# 2015_FDP_PROPULSION.net
KiCad netlist of a schematic drawn in Altium Designer
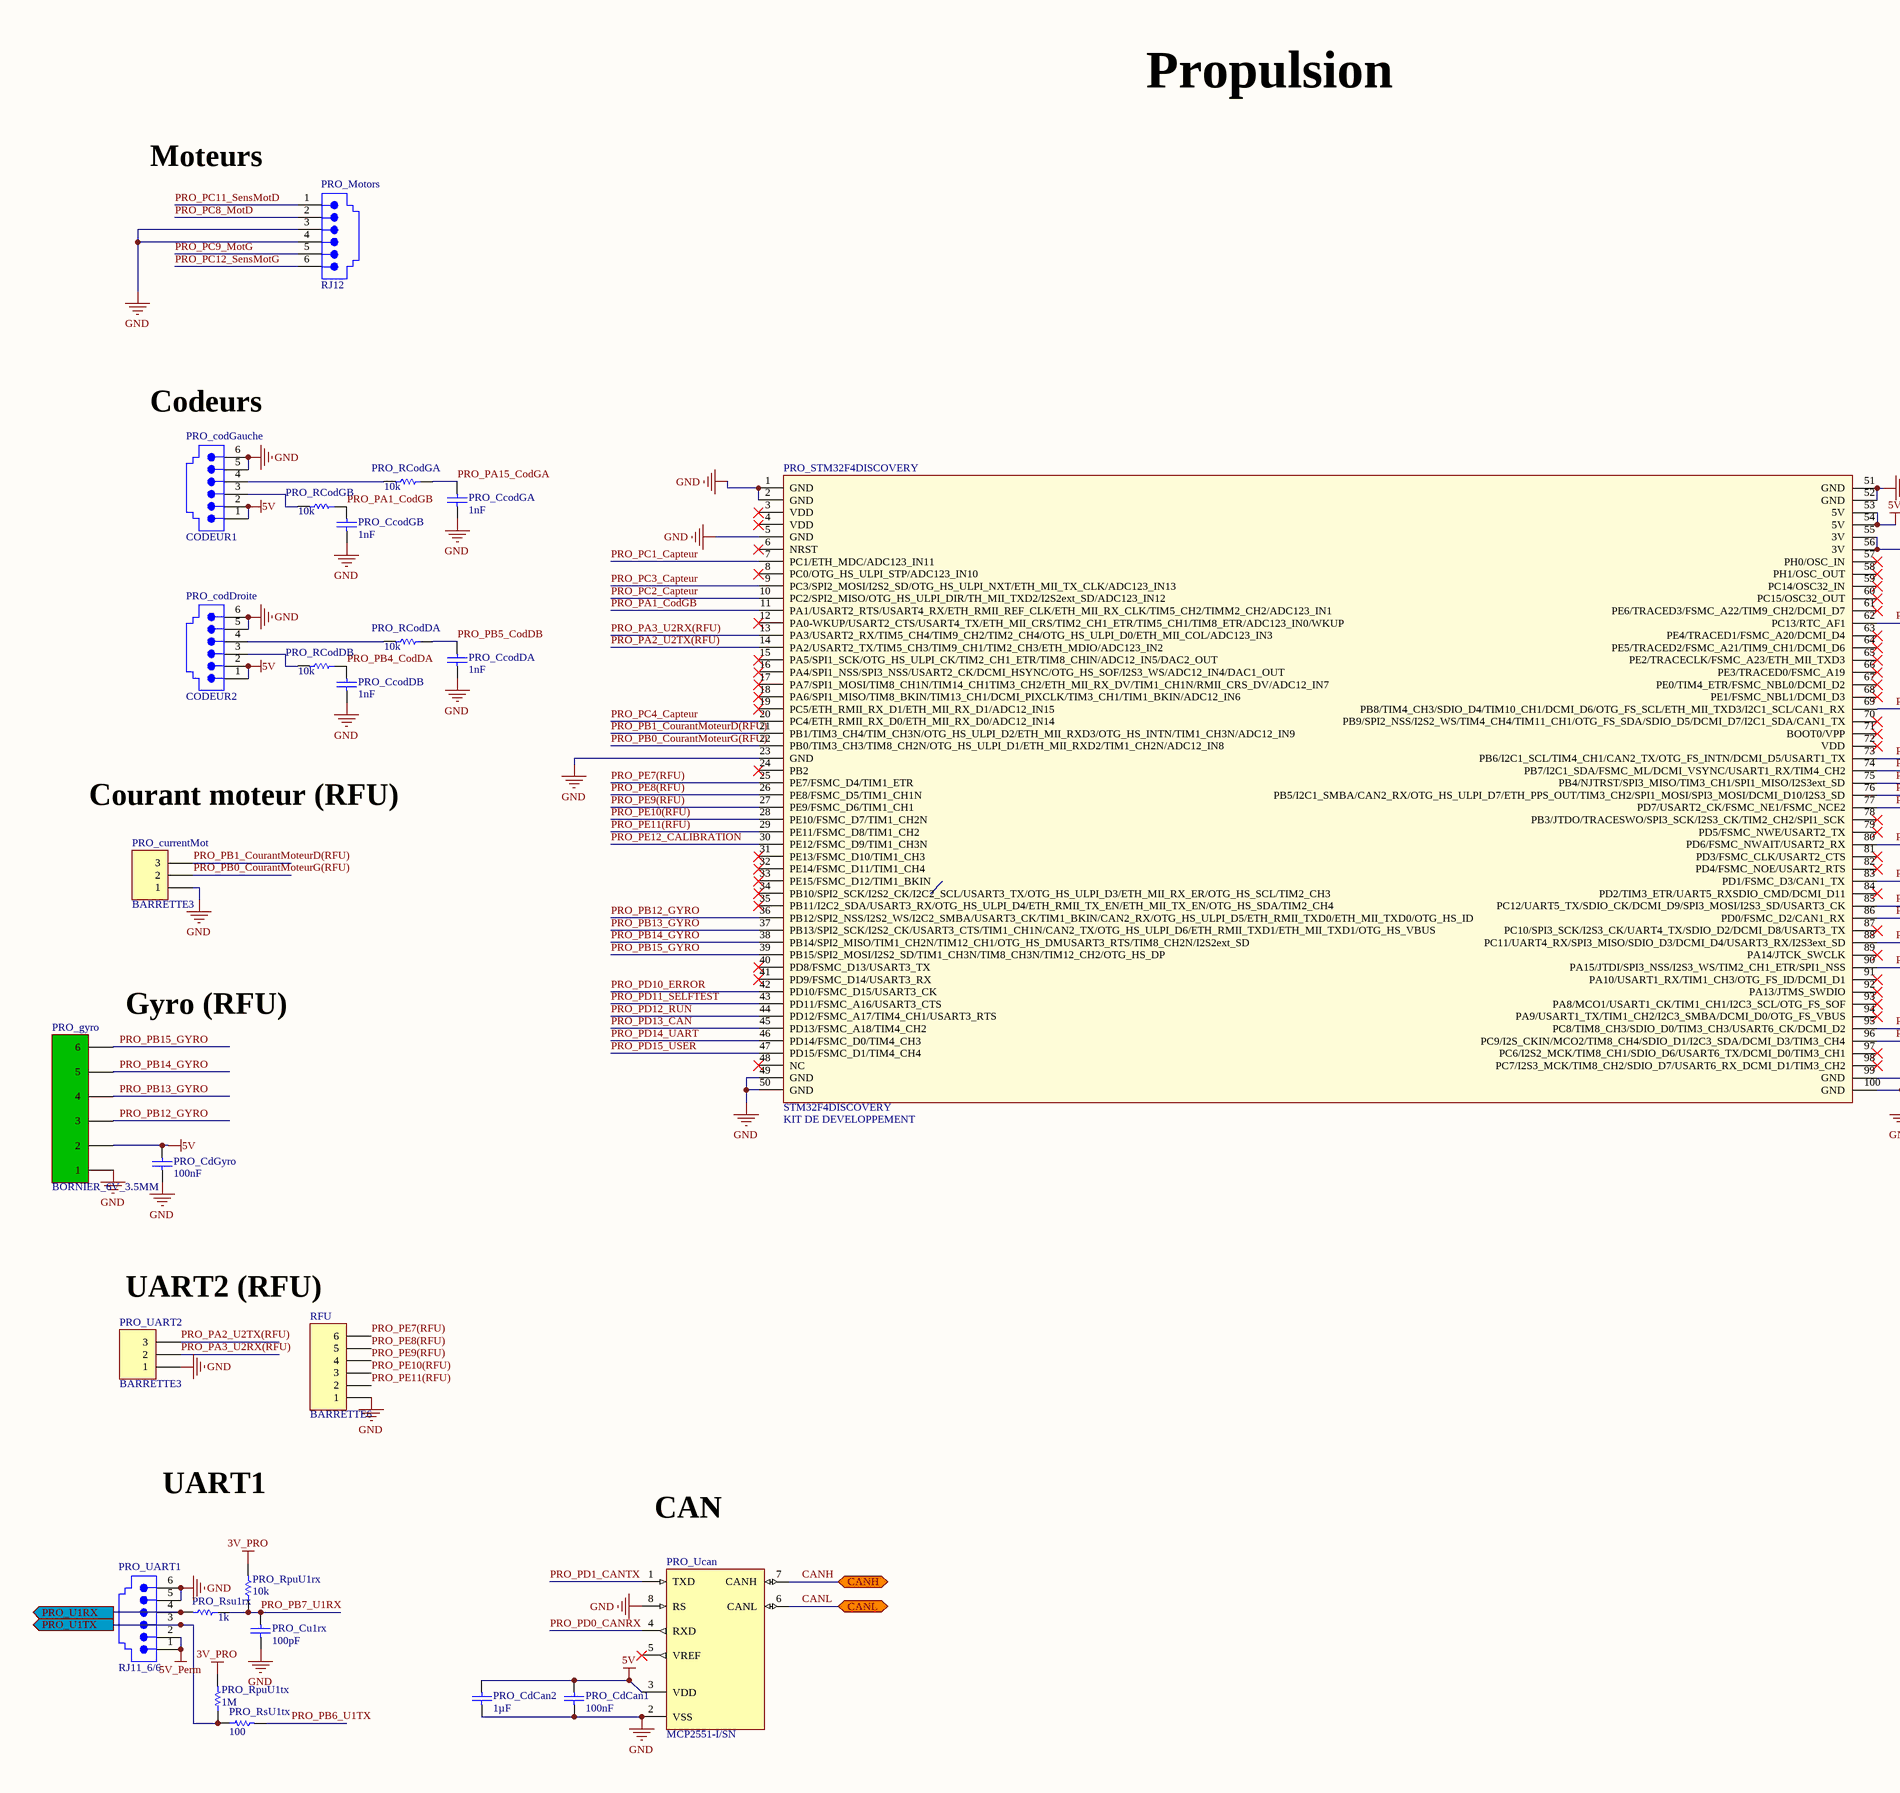
[diagram p0: 2015_FDP_PROPULSION.SchDoc, left]
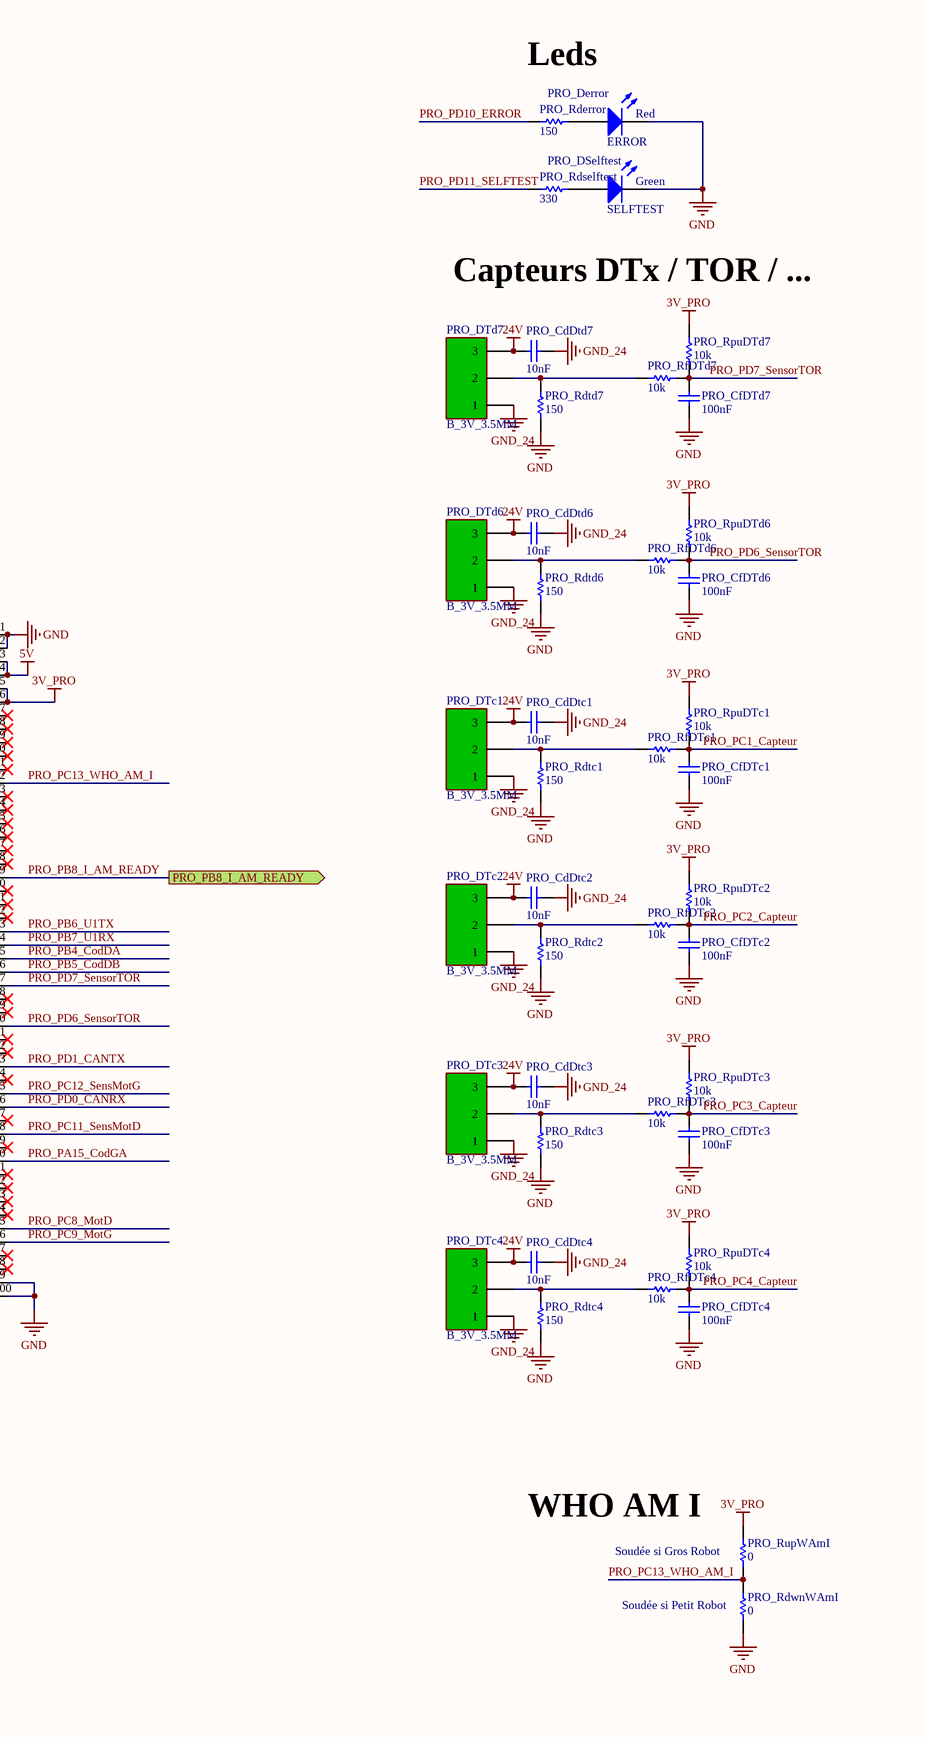
[diagram p1: 2015_FDP_PROPULSION.SchDoc, right]

(export (version "E")
  (design (tool "Eeschema 10.0.6"))
  (components
    (comp (ref "PRO_CcodDA")
      (value "1nF")
      (footprint "C0805_N")
      (description "Capacitor")
      (fields (field (name "PUBLISHER") "Altium Limited"))
      (libsource (lib "_ROBOT") (part "Condensateur"))
    )
    (comp (ref "PRO_CcodDB")
      (value "1nF")
      (footprint "C0805_N")
      (description "Capacitor")
      (fields (field (name "PUBLISHER") "Altium Limited"))
      (libsource (lib "_ROBOT") (part "Condensateur"))
    )
    (comp (ref "PRO_CcodGA")
      (value "1nF")
      (footprint "C0805_N")
      (description "Capacitor")
      (fields (field (name "PUBLISHER") "Altium Limited"))
      (libsource (lib "_ROBOT") (part "Condensateur"))
    )
    (comp (ref "PRO_CcodGB")
      (value "1nF")
      (footprint "C0805_N")
      (description "Capacitor")
      (fields (field (name "PUBLISHER") "Altium Limited"))
      (libsource (lib "_ROBOT") (part "Condensateur"))
    )
    (comp (ref "PRO_CdCan1")
      (value "100nF")
      (footprint "C0805_N")
      (description "Capacitor")
      (fields (field (name "PUBLISHER") "Altium Limited"))
      (libsource (lib "_ROBOT") (part "Condensateur"))
    )
    (comp (ref "PRO_CdCan2")
      (value "1µF")
      (footprint "C0805_N")
      (description "Capacitor")
      (fields (field (name "PUBLISHER") "Altium Limited"))
      (libsource (lib "_ROBOT") (part "Condensateur"))
    )
    (comp (ref "PRO_CdDtc1")
      (value "10nF")
      (footprint "C0805_N")
      (description "Capacitor")
      (fields (field (name "PUBLISHER") "Altium Limited"))
      (libsource (lib "_ROBOT") (part "Condensateur"))
    )
    (comp (ref "PRO_CdDtc2")
      (value "10nF")
      (footprint "C0805_N")
      (description "Capacitor")
      (fields (field (name "PUBLISHER") "Altium Limited"))
      (libsource (lib "_ROBOT") (part "Condensateur"))
    )
    (comp (ref "PRO_CdDtc3")
      (value "10nF")
      (footprint "C0805_N")
      (description "Capacitor")
      (fields (field (name "PUBLISHER") "Altium Limited"))
      (libsource (lib "_ROBOT") (part "Condensateur"))
    )
    (comp (ref "PRO_CdDtc4")
      (value "10nF")
      (footprint "C0805_N")
      (description "Capacitor")
      (fields (field (name "PUBLISHER") "Altium Limited"))
      (libsource (lib "_ROBOT") (part "Condensateur"))
    )
    (comp (ref "PRO_CdDtd6")
      (value "10nF")
      (footprint "C0805_N")
      (description "Capacitor")
      (fields (field (name "PUBLISHER") "Altium Limited"))
      (libsource (lib "_ROBOT") (part "Condensateur"))
    )
    (comp (ref "PRO_CdDtd7")
      (value "10nF")
      (footprint "C0805_N")
      (description "Capacitor")
      (fields (field (name "PUBLISHER") "Altium Limited"))
      (libsource (lib "_ROBOT") (part "Condensateur"))
    )
    (comp (ref "PRO_CdGyro")
      (value "100nF")
      (footprint "C0805_N")
      (description "Capacitor")
      (fields (field (name "PUBLISHER") "Altium Limited"))
      (libsource (lib "_ROBOT") (part "Condensateur"))
    )
    (comp (ref "PRO_CfDTc1")
      (value "100nF")
      (footprint "C0805_N")
      (description "Capacitor")
      (fields (field (name "PUBLISHER") "Altium Limited"))
      (libsource (lib "_ROBOT") (part "Condensateur"))
    )
    (comp (ref "PRO_CfDTc2")
      (value "100nF")
      (footprint "C0805_N")
      (description "Capacitor")
      (fields (field (name "PUBLISHER") "Altium Limited"))
      (libsource (lib "_ROBOT") (part "Condensateur"))
    )
    (comp (ref "PRO_CfDTc3")
      (value "100nF")
      (footprint "C0805_N")
      (description "Capacitor")
      (fields (field (name "PUBLISHER") "Altium Limited"))
      (libsource (lib "_ROBOT") (part "Condensateur"))
    )
    (comp (ref "PRO_CfDTc4")
      (value "100nF")
      (footprint "C0805_N")
      (description "Capacitor")
      (fields (field (name "PUBLISHER") "Altium Limited"))
      (libsource (lib "_ROBOT") (part "Condensateur"))
    )
    (comp (ref "PRO_CfDTd6")
      (value "100nF")
      (footprint "C0805_N")
      (description "Capacitor")
      (fields (field (name "PUBLISHER") "Altium Limited"))
      (libsource (lib "_ROBOT") (part "Condensateur"))
    )
    (comp (ref "PRO_CfDTd7")
      (value "100nF")
      (footprint "C0805_N")
      (description "Capacitor")
      (fields (field (name "PUBLISHER") "Altium Limited"))
      (libsource (lib "_ROBOT") (part "Condensateur"))
    )
    (comp (ref "PRO_codDroite")
      (value "CODEUR2")
      (footprint "RJ11_6/6 - droit")
      (description "Right Angle, Standard Profile, Offset Latch DECconnect, Flangeless PCB Jack")
      (fields (field (name "PUBLISHER") "Altium Limited"))
      (libsource (lib "miniprojet") (part "RJ11_6/6"))
    )
    (comp (ref "PRO_codGauche")
      (value "CODEUR1")
      (footprint "RJ11_6/6 - droit")
      (description "Right Angle, Standard Profile, Offset Latch DECconnect, Flangeless PCB Jack")
      (fields (field (name "PUBLISHER") "Altium Limited"))
      (libsource (lib "miniprojet") (part "RJ11_6/6"))
    )
    (comp (ref "PRO_Cu1rx")
      (value "100pF")
      (footprint "C0805_N")
      (description "Capacitor")
      (fields (field (name "PUBLISHER") "Altium Limited"))
      (libsource (lib "_ROBOT") (part "Condensateur"))
    )
    (comp (ref "PRO_currentMot")
      (value "BARRETTE3")
      (footprint "HE14_3")
      (description "Header, 3-Pin")
      (fields (field (name "PUBLISHER") "Altium Limited"))
      (libsource (lib "Connecteur") (part "BARRETTE3"))
    )
    (comp (ref "PRO_Derror")
      (value "ERROR")
      (footprint "LED_0805")
      (description "Typical LED")
      (fields (field (name "PUBLISHER") "Altium Limited"))
      (libsource (lib "_ROBOT") (part "LED"))
    )
    (comp (ref "PRO_DSelftest")
      (value "SELFTEST")
      (footprint "LED_0805")
      (description "Typical LED")
      (fields (field (name "PUBLISHER") "Altium Limited"))
      (libsource (lib "_ROBOT") (part "LED"))
    )
    (comp (ref "PRO_DTc1")
      (value "B_3V_3.5MM")
      (footprint "BORNIER_3V_3.5MM")
      (libsource (lib "Connecteur") (part "BORNIER_3V_3.5MM"))
    )
    (comp (ref "PRO_DTc2")
      (value "B_3V_3.5MM")
      (footprint "BORNIER_3V_3.5MM")
      (libsource (lib "Connecteur") (part "BORNIER_3V_3.5MM"))
    )
    (comp (ref "PRO_DTc3")
      (value "B_3V_3.5MM")
      (footprint "BORNIER_3V_3.5MM")
      (libsource (lib "Connecteur") (part "BORNIER_3V_3.5MM"))
    )
    (comp (ref "PRO_DTc4")
      (value "B_3V_3.5MM")
      (footprint "BORNIER_3V_3.5MM")
      (libsource (lib "Connecteur") (part "BORNIER_3V_3.5MM"))
    )
    (comp (ref "PRO_DTd6")
      (value "B_3V_3.5MM")
      (footprint "BORNIER_3V_3.5MM")
      (libsource (lib "Connecteur") (part "BORNIER_3V_3.5MM"))
    )
    (comp (ref "PRO_DTd7")
      (value "B_3V_3.5MM")
      (footprint "BORNIER_3V_3.5MM")
      (libsource (lib "Connecteur") (part "BORNIER_3V_3.5MM"))
    )
    (comp (ref "PRO_gyro")
      (value "BORNIER_6V_3.5MM")
      (footprint "BORNIER_6V_3.5MM")
      (libsource (lib "Connecteur") (part "BORNIER_6V_3.5MM"))
    )
    (comp (ref "PRO_Motors")
      (value "RJ12")
      (footprint "RJ11_6/6 - droit")
      (description "Right Angle, Standard Profile, Offset Latch DECconnect, Flangeless PCB Jack")
      (fields (field (name "PUBLISHER") "Altium Limited"))
      (libsource (lib "Connecteur") (part "RJ11_6/6"))
    )
    (comp (ref "PRO_RCodDA")
      (value "10k")
      (footprint "R1206_N")
      (description "Resistor")
      (fields (field (name "PUBLISHER") "Altium Limited"))
      (libsource (lib "_ROBOT") (part "Resistor"))
    )
    (comp (ref "PRO_RCodDB")
      (value "10k")
      (footprint "R1206_N")
      (description "Resistor")
      (fields (field (name "PUBLISHER") "Altium Limited"))
      (libsource (lib "_ROBOT") (part "Resistor"))
    )
    (comp (ref "PRO_RCodGA")
      (value "10k")
      (footprint "R1206_N")
      (description "Resistor")
      (fields (field (name "PUBLISHER") "Altium Limited"))
      (libsource (lib "_ROBOT") (part "Resistor"))
    )
    (comp (ref "PRO_RCodGB")
      (value "10k")
      (footprint "R1206_N")
      (description "Resistor")
      (fields (field (name "PUBLISHER") "Altium Limited"))
      (libsource (lib "_ROBOT") (part "Resistor"))
    )
    (comp (ref "PRO_Rderror")
      (value "150")
      (footprint "R1206_N")
      (description "Resistor")
      (fields (field (name "PUBLISHER") "Altium Limited"))
      (libsource (lib "_ROBOT") (part "Resistor"))
    )
    (comp (ref "PRO_Rdselftest")
      (value "330")
      (footprint "R1206_N")
      (description "Resistor")
      (fields (field (name "PUBLISHER") "Altium Limited"))
      (libsource (lib "_ROBOT") (part "Resistor"))
    )
    (comp (ref "PRO_Rdtc1")
      (value "150")
      (footprint "R1206_N")
      (description "Resistor")
      (fields (field (name "PUBLISHER") "Altium Limited"))
      (libsource (lib "_ROBOT") (part "Resistor"))
    )
    (comp (ref "PRO_Rdtc2")
      (value "150")
      (footprint "R1206_N")
      (description "Resistor")
      (fields (field (name "PUBLISHER") "Altium Limited"))
      (libsource (lib "_ROBOT") (part "Resistor"))
    )
    (comp (ref "PRO_Rdtc3")
      (value "150")
      (footprint "R1206_N")
      (description "Resistor")
      (fields (field (name "PUBLISHER") "Altium Limited"))
      (libsource (lib "_ROBOT") (part "Resistor"))
    )
    (comp (ref "PRO_Rdtc4")
      (value "150")
      (footprint "R1206_N")
      (description "Resistor")
      (fields (field (name "PUBLISHER") "Altium Limited"))
      (libsource (lib "_ROBOT") (part "Resistor"))
    )
    (comp (ref "PRO_Rdtd6")
      (value "150")
      (footprint "R1206_N")
      (description "Resistor")
      (fields (field (name "PUBLISHER") "Altium Limited"))
      (libsource (lib "_ROBOT") (part "Resistor"))
    )
    (comp (ref "PRO_Rdtd7")
      (value "150")
      (footprint "R1206_N")
      (description "Resistor")
      (fields (field (name "PUBLISHER") "Altium Limited"))
      (libsource (lib "_ROBOT") (part "Resistor"))
    )
    (comp (ref "PRO_RdwnWAmI")
      (value "0")
      (footprint "R1206_N")
      (description "Resistor")
      (fields (field (name "PUBLISHER") "Altium Limited"))
      (libsource (lib "_ROBOT") (part "Resistor"))
    )
    (comp (ref "PRO_RfDTc1")
      (value "10k")
      (footprint "R1206_N")
      (description "Resistor")
      (fields (field (name "PUBLISHER") "Altium Limited"))
      (libsource (lib "_ROBOT") (part "Resistor"))
    )
    (comp (ref "PRO_RfDTc2")
      (value "10k")
      (footprint "R1206_N")
      (description "Resistor")
      (fields (field (name "PUBLISHER") "Altium Limited"))
      (libsource (lib "_ROBOT") (part "Resistor"))
    )
    (comp (ref "PRO_RfDTc3")
      (value "10k")
      (footprint "R1206_N")
      (description "Resistor")
      (fields (field (name "PUBLISHER") "Altium Limited"))
      (libsource (lib "_ROBOT") (part "Resistor"))
    )
    (comp (ref "PRO_RfDTc4")
      (value "10k")
      (footprint "R1206_N")
      (description "Resistor")
      (fields (field (name "PUBLISHER") "Altium Limited"))
      (libsource (lib "_ROBOT") (part "Resistor"))
    )
    (comp (ref "PRO_RfDTd6")
      (value "10k")
      (footprint "R1206_N")
      (description "Resistor")
      (fields (field (name "PUBLISHER") "Altium Limited"))
      (libsource (lib "_ROBOT") (part "Resistor"))
    )
    (comp (ref "PRO_RfDTd7")
      (value "10k")
      (footprint "R1206_N")
      (description "Resistor")
      (fields (field (name "PUBLISHER") "Altium Limited"))
      (libsource (lib "_ROBOT") (part "Resistor"))
    )
    (comp (ref "PRO_RpuDTc1")
      (value "10k")
      (footprint "R1206_N")
      (description "Resistor")
      (fields (field (name "PUBLISHER") "Altium Limited"))
      (libsource (lib "_ROBOT") (part "Resistor"))
    )
    (comp (ref "PRO_RpuDTc2")
      (value "10k")
      (footprint "R1206_N")
      (description "Resistor")
      (fields (field (name "PUBLISHER") "Altium Limited"))
      (libsource (lib "_ROBOT") (part "Resistor"))
    )
    (comp (ref "PRO_RpuDTc3")
      (value "10k")
      (footprint "R1206_N")
      (description "Resistor")
      (fields (field (name "PUBLISHER") "Altium Limited"))
      (libsource (lib "_ROBOT") (part "Resistor"))
    )
    (comp (ref "PRO_RpuDTc4")
      (value "10k")
      (footprint "R1206_N")
      (description "Resistor")
      (fields (field (name "PUBLISHER") "Altium Limited"))
      (libsource (lib "_ROBOT") (part "Resistor"))
    )
    (comp (ref "PRO_RpuDTd6")
      (value "10k")
      (footprint "R1206_N")
      (description "Resistor")
      (fields (field (name "PUBLISHER") "Altium Limited"))
      (libsource (lib "_ROBOT") (part "Resistor"))
    )
    (comp (ref "PRO_RpuDTd7")
      (value "10k")
      (footprint "R1206_N")
      (description "Resistor")
      (fields (field (name "PUBLISHER") "Altium Limited"))
      (libsource (lib "_ROBOT") (part "Resistor"))
    )
    (comp (ref "PRO_RpuU1rx")
      (value "10k")
      (footprint "R1206_N")
      (description "Resistor")
      (fields (field (name "PUBLISHER") "Altium Limited"))
      (libsource (lib "_ROBOT") (part "Resistor"))
    )
    (comp (ref "PRO_RpuU1tx")
      (value "1M")
      (footprint "R1206_N")
      (description "Resistor")
      (fields (field (name "PUBLISHER") "Altium Limited"))
      (libsource (lib "_ROBOT") (part "Resistor"))
    )
    (comp (ref "PRO_Rsu1rx")
      (value "1k")
      (footprint "R1206_N")
      (description "Resistor")
      (fields (field (name "PUBLISHER") "Altium Limited"))
      (libsource (lib "_ROBOT") (part "Resistor"))
    )
    (comp (ref "PRO_RsU1tx")
      (value "100")
      (footprint "R1206_N")
      (description "Resistor")
      (fields (field (name "PUBLISHER") "Altium Limited"))
      (libsource (lib "_ROBOT") (part "Resistor"))
    )
    (comp (ref "PRO_RupWAmI")
      (value "0")
      (footprint "R1206_N")
      (description "Resistor")
      (fields (field (name "PUBLISHER") "Altium Limited"))
      (libsource (lib "_ROBOT") (part "Resistor"))
    )
    (comp (ref "PRO_STM32F4DISCOVERY")
      (value "STM32F4DISCOVERY")
      (footprint "STM32_F4DISCOVERY")
      (description "KIT DE DEVELOPPEMENT POUR MICROCONTROLEUR STM32F407VGT6")
      (fields (field (name "TYPE") "KIT DE DEVELOPPEMENT"))
      (libsource (lib "circuits integres") (part "STM32F4DISCOVERY"))
    )
    (comp (ref "PRO_UART1")
      (value "RJ11_6/6")
      (footprint "RJ11_6/6 - droit")
      (description "Right Angle, Standard Profile, Offset Latch DECconnect, Flangeless PCB Jack")
      (fields (field (name "PUBLISHER") "Altium Limited"))
      (libsource (lib "Connecteur") (part "RJ11_6/6"))
    )
    (comp (ref "PRO_UART2")
      (value "BARRETTE3")
      (footprint "HE14_3")
      (description "Header, 3-Pin")
      (fields (field (name "PUBLISHER") "Altium Limited"))
      (libsource (lib "Connecteur") (part "BARRETTE3"))
    )
    (comp (ref "PRO_Ucan")
      (value "MCP2551-I/SN")
      (footprint "SO8_N")
      (description "High-Speed CAN Transceiver, 8-Pin SOIC, Industrial Temperature")
      (fields (field (name "PUBLISHER") "Damien Guitton"))
      (libsource (lib "Circuit intégré") (part "MCP2551-I/SN"))
    )
    (comp (ref "RFU")
      (value "BARRETTE6")
      (footprint "HE14_6")
      (description "Header, 6-Pin")
      (fields (field (name "PUBLISHER") "Altium Limited"))
      (libsource (lib "Connecteur") (part "BARRETTE6"))
    )
  )
  (nets
    (net (code "1") (name "/CANH") (class "Default")
      (node (ref "PRO_Ucan") (pin "7") (pinfunction "CANH_7") (pintype "bidirectional"))
    )
    (net (code "2") (name "/CANL") (class "Default")
      (node (ref "PRO_Ucan") (pin "6") (pinfunction "CANL_6") (pintype "bidirectional"))
    )
    (net (code "3") (name "/PRO_PA1_CodGB") (class "Default")
      (node (ref "PRO_CcodGB") (pin "2") (pinfunction "2_2") (pintype "passive"))
      (node (ref "PRO_RCodGB") (pin "1") (pinfunction "1_1") (pintype "passive"))
      (node (ref "PRO_STM32F4DISCOVERY") (pin "11") (pinfunction "PA1/USART2_RTS/USART4_RX/ETH_RMII_REF_CLK/ETH_MII_RX_CLK/TIM5_CH2/TIMM2_CH2/ADC123_IN1_11") (pintype "passive"))
    )
    (net (code "4") (name "/PRO_PA2_U2TX(RFU)") (class "Default")
      (node (ref "PRO_STM32F4DISCOVERY") (pin "14") (pinfunction "PA2/USART2_TX/TIM5_CH3/TIM9_CH1/TIM2_CH3/ETH_MDIO/ADC123_IN2_14") (pintype "passive"))
      (node (ref "PRO_UART2") (pin "3") (pinfunction "3_3") (pintype "passive"))
    )
    (net (code "5") (name "/PRO_PA3_U2RX(RFU)") (class "Default")
      (node (ref "PRO_STM32F4DISCOVERY") (pin "13") (pinfunction "PA3/USART2_RX/TIM5_CH4/TIM9_CH2/TIM2_CH4/OTG_HS_ULPI_D0/ETH_MII_COL/ADC123_IN3_13") (pintype "passive"))
      (node (ref "PRO_UART2") (pin "2") (pinfunction "2_2") (pintype "passive"))
    )
    (net (code "6") (name "/PRO_PA15_CodGA") (class "Default")
      (node (ref "PRO_CcodGA") (pin "2") (pinfunction "2_2") (pintype "passive"))
      (node (ref "PRO_RCodGA") (pin "1") (pinfunction "1_1") (pintype "passive"))
      (node (ref "PRO_STM32F4DISCOVERY") (pin "90") (pinfunction "PA15/JTDI/SPI3_NSS/I2S3_WS/TIM2_CH1_ETR/SPI1_NSS_90") (pintype "passive"))
    )
    (net (code "7") (name "/PRO_PB0_CourantMoteurG(RFU)") (class "Default")
      (node (ref "PRO_STM32F4DISCOVERY") (pin "22") (pinfunction "PB0/TIM3_CH3/TIM8_CH2N/OTG_HS_ULPI_D1/ETH_MII_RXD2/TIM1_CH2N/ADC12_IN8_22") (pintype "passive"))
      (node (ref "PRO_currentMot") (pin "2") (pinfunction "2_2") (pintype "passive"))
    )
    (net (code "8") (name "/PRO_PB1_CourantMoteurD(RFU)") (class "Default")
      (node (ref "PRO_STM32F4DISCOVERY") (pin "21") (pinfunction "PB1/TIM3_CH4/TIM_CH3N/OTG_HS_ULPI_D2/ETH_MII_RXD3/OTG_HS_INTN/TIM1_CH3N/ADC12_IN9_21") (pintype "passive"))
      (node (ref "PRO_currentMot") (pin "3") (pinfunction "3_3") (pintype "passive"))
    )
    (net (code "9") (name "/PRO_PB4_CodDA") (class "Default")
      (node (ref "PRO_CcodDB") (pin "2") (pinfunction "2_2") (pintype "passive"))
      (node (ref "PRO_RCodDB") (pin "1") (pinfunction "1_1") (pintype "passive"))
      (node (ref "PRO_STM32F4DISCOVERY") (pin "75") (pinfunction "PB4/NJTRST/SPI3_MISO/TIM3_CH1/SPI1_MISO/I2S3ext_SD_75") (pintype "passive"))
    )
    (net (code "10") (name "/PRO_PB5_CodDB") (class "Default")
      (node (ref "PRO_CcodDA") (pin "2") (pinfunction "2_2") (pintype "passive"))
      (node (ref "PRO_RCodDA") (pin "1") (pinfunction "1_1") (pintype "passive"))
      (node (ref "PRO_STM32F4DISCOVERY") (pin "76") (pinfunction "PB5/I2C1_SMBA/CAN2_RX/OTG_HS_ULPI_D7/ETH_PPS_OUT/TIM3_CH2/SPI1_MOSI/SPI3_MOSI/DCMI_D10/I2S3_SD_76") (pintype "passive"))
    )
    (net (code "11") (name "/PRO_PB6_U1TX") (class "Default")
      (node (ref "PRO_RsU1tx") (pin "2") (pinfunction "2_2") (pintype "passive"))
      (node (ref "PRO_STM32F4DISCOVERY") (pin "73") (pinfunction "PB6/I2C1_SCL/TIM4_CH1/CAN2_TX/OTG_FS_INTN/DCMI_D5/USART1_TX_73") (pintype "passive"))
    )
    (net (code "12") (name "/PRO_PB7_U1RX") (class "Default")
      (node (ref "PRO_Cu1rx") (pin "2") (pinfunction "2_2") (pintype "passive"))
      (node (ref "PRO_RpuU1rx") (pin "1") (pinfunction "1_1") (pintype "passive"))
      (node (ref "PRO_Rsu1rx") (pin "1") (pinfunction "1_1") (pintype "passive"))
      (node (ref "PRO_STM32F4DISCOVERY") (pin "74") (pinfunction "PB7/I2C1_SDA/FSMC_ML/DCMI_VSYNC/USART1_RX/TIM4_CH2_74") (pintype "passive"))
    )
    (net (code "13") (name "/PRO_PB8_I_AM_READY") (class "Default")
      (node (ref "PRO_STM32F4DISCOVERY") (pin "69") (pinfunction "PB8/TIM4_CH3/SDIO_D4/TIM10_CH1/DCMI_D6/OTG_FS_SCL/ETH_MII_TXD3/I2C1_SCL/CAN1_RX_69") (pintype "passive"))
    )
    (net (code "14") (name "/PRO_PB12_GYRO") (class "Default")
      (node (ref "PRO_STM32F4DISCOVERY") (pin "36") (pinfunction "PB12/SPI2_NSS/I2S2_WS/I2C2_SMBA/USART3_CK/TIM1_BKIN/CAN2_RX/OTG_HS_ULPI_D5/ETH_RMII_TXD0/ETH_MII_TXD0/OTG_HS_ID_36") (pintype "passive"))
      (node (ref "PRO_gyro") (pin "3") (pinfunction "3_3") (pintype "passive"))
    )
    (net (code "15") (name "/PRO_PB13_GYRO") (class "Default")
      (node (ref "PRO_STM32F4DISCOVERY") (pin "37") (pinfunction "PB13/SPI2_SCK/I2S2_CK/USART3_CTS/TIM1_CH1N/CAN2_TX/OTG_HS_ULPI_D6/ETH_RMII_TXD1/ETH_MII_TXD1/OTG_HS_VBUS_37") (pintype "passive"))
      (node (ref "PRO_gyro") (pin "4") (pinfunction "4_4") (pintype "passive"))
    )
    (net (code "16") (name "/PRO_PB14_GYRO") (class "Default")
      (node (ref "PRO_STM32F4DISCOVERY") (pin "38") (pinfunction "PB14/SPI2_MISO/TIM1_CH2N/TIM12_CH1/OTG_HS_DMUSART3_RTS/TIM8_CH2N/I2S2ext_SD_38") (pintype "passive"))
      (node (ref "PRO_gyro") (pin "5") (pinfunction "5_5") (pintype "passive"))
    )
    (net (code "17") (name "/PRO_PB15_GYRO") (class "Default")
      (node (ref "PRO_STM32F4DISCOVERY") (pin "39") (pinfunction "PB15/SPI2_MOSI/I2S2_SD/TIM1_CH3N/TIM8_CH3N/TIM12_CH2/OTG_HS_DP_39") (pintype "passive"))
      (node (ref "PRO_gyro") (pin "6") (pinfunction "6_6") (pintype "passive"))
    )
    (net (code "18") (name "/PRO_PC1_Capteur") (class "Default")
      (node (ref "PRO_CfDTc1") (pin "2") (pinfunction "2_2") (pintype "passive"))
      (node (ref "PRO_RfDTc1") (pin "2") (pinfunction "2_2") (pintype "passive"))
      (node (ref "PRO_RpuDTc1") (pin "1") (pinfunction "1_1") (pintype "passive"))
      (node (ref "PRO_STM32F4DISCOVERY") (pin "7") (pinfunction "PC1/ETH_MDC/ADC123_IN11_7") (pintype "passive"))
    )
    (net (code "19") (name "/PRO_PC2_Capteur") (class "Default")
      (node (ref "PRO_CfDTc2") (pin "2") (pinfunction "2_2") (pintype "passive"))
      (node (ref "PRO_RfDTc2") (pin "2") (pinfunction "2_2") (pintype "passive"))
      (node (ref "PRO_RpuDTc2") (pin "1") (pinfunction "1_1") (pintype "passive"))
      (node (ref "PRO_STM32F4DISCOVERY") (pin "10") (pinfunction "PC2/SPI2_MISO/OTG_HS_ULPI_DIR/TH_MII_TXD2/I2S2ext_SD/ADC123_IN12_10") (pintype "passive"))
    )
    (net (code "20") (name "/PRO_PC3_Capteur") (class "Default")
      (node (ref "PRO_CfDTc3") (pin "2") (pinfunction "2_2") (pintype "passive"))
      (node (ref "PRO_RfDTc3") (pin "2") (pinfunction "2_2") (pintype "passive"))
      (node (ref "PRO_RpuDTc3") (pin "1") (pinfunction "1_1") (pintype "passive"))
      (node (ref "PRO_STM32F4DISCOVERY") (pin "9") (pinfunction "PC3/SPI2_MOSI/I2S2_SD/OTG_HS_ULPI_NXT/ETH_MII_TX_CLK/ADC123_IN13_9") (pintype "passive"))
    )
    (net (code "21") (name "/PRO_PC4_Capteur") (class "Default")
      (node (ref "PRO_CfDTc4") (pin "2") (pinfunction "2_2") (pintype "passive"))
      (node (ref "PRO_RfDTc4") (pin "2") (pinfunction "2_2") (pintype "passive"))
      (node (ref "PRO_RpuDTc4") (pin "1") (pinfunction "1_1") (pintype "passive"))
      (node (ref "PRO_STM32F4DISCOVERY") (pin "20") (pinfunction "PC4/ETH_RMII_RX_D0/ETH_MII_RX_D0/ADC12_IN14_20") (pintype "passive"))
    )
    (net (code "22") (name "/PRO_PC8_MotD") (class "Default")
      (node (ref "PRO_Motors") (pin "2") (pinfunction "2_2") (pintype "passive"))
      (node (ref "PRO_STM32F4DISCOVERY") (pin "95") (pinfunction "PC8/TIM8_CH3/SDIO_D0/TIM3_CH3/USART6_CK/DCMI_D2_95") (pintype "passive"))
    )
    (net (code "23") (name "/PRO_PC9_MotG") (class "Default")
      (node (ref "PRO_Motors") (pin "5") (pinfunction "5_5") (pintype "passive"))
      (node (ref "PRO_STM32F4DISCOVERY") (pin "96") (pinfunction "PC9/I2S_CKIN/MCO2/TIM8_CH4/SDIO_D1/I2C3_SDA/DCMI_D3/TIM3_CH4_96") (pintype "passive"))
    )
    (net (code "24") (name "/PRO_PC11_SensMotD") (class "Default")
      (node (ref "PRO_Motors") (pin "1") (pinfunction "1_1") (pintype "passive"))
      (node (ref "PRO_STM32F4DISCOVERY") (pin "88") (pinfunction "PC11/UART4_RX/SPI3_MISO/SDIO_D3/DCMI_D4/USART3_RX/I2S3ext_SD_88") (pintype "passive"))
    )
    (net (code "25") (name "/PRO_PC12_SensMotG") (class "Default")
      (node (ref "PRO_Motors") (pin "6") (pinfunction "6_6") (pintype "passive"))
      (node (ref "PRO_STM32F4DISCOVERY") (pin "85") (pinfunction "PC12/UART5_TX/SDIO_CK/DCMI_D9/SPI3_MOSI/I2S3_SD/USART3_CK_85") (pintype "passive"))
    )
    (net (code "26") (name "/PRO_PC13_WHO_AM_I") (class "Default")
      (node (ref "PRO_RdwnWAmI") (pin "2") (pinfunction "2_2") (pintype "passive"))
      (node (ref "PRO_RupWAmI") (pin "1") (pinfunction "1_1") (pintype "passive"))
      (node (ref "PRO_STM32F4DISCOVERY") (pin "62") (pinfunction "PC13/RTC_AF1_62") (pintype "passive"))
    )
    (net (code "27") (name "/PRO_PD0_CANRX") (class "Default")
      (node (ref "PRO_STM32F4DISCOVERY") (pin "86") (pinfunction "PD0/FSMC_D2/CAN1_RX_86") (pintype "passive"))
      (node (ref "PRO_Ucan") (pin "4") (pinfunction "RXD_4") (pintype "output"))
    )
    (net (code "28") (name "/PRO_PD1_CANTX") (class "Default")
      (node (ref "PRO_STM32F4DISCOVERY") (pin "83") (pinfunction "PD1/FSMC_D3/CAN1_TX_83") (pintype "passive"))
      (node (ref "PRO_Ucan") (pin "1") (pinfunction "TXD_1") (pintype "input"))
    )
    (net (code "29") (name "/PRO_PD6_SensorTOR") (class "Default")
      (node (ref "PRO_CfDTd6") (pin "2") (pinfunction "2_2") (pintype "passive"))
      (node (ref "PRO_RfDTd6") (pin "2") (pinfunction "2_2") (pintype "passive"))
      (node (ref "PRO_RpuDTd6") (pin "1") (pinfunction "1_1") (pintype "passive"))
      (node (ref "PRO_STM32F4DISCOVERY") (pin "80") (pinfunction "PD6/FSMC_NWAIT/USART2_RX_80") (pintype "passive"))
    )
    (net (code "30") (name "/PRO_PD7_SensorTOR") (class "Default")
      (node (ref "PRO_CfDTd7") (pin "2") (pinfunction "2_2") (pintype "passive"))
      (node (ref "PRO_RfDTd7") (pin "2") (pinfunction "2_2") (pintype "passive"))
      (node (ref "PRO_RpuDTd7") (pin "1") (pinfunction "1_1") (pintype "passive"))
      (node (ref "PRO_STM32F4DISCOVERY") (pin "77") (pinfunction "PD7/USART2_CK/FSMC_NE1/FSMC_NCE2_77") (pintype "passive"))
    )
    (net (code "31") (name "/PRO_PD10_ERROR") (class "Default")
      (node (ref "PRO_Rderror") (pin "1") (pinfunction "1_1") (pintype "passive"))
      (node (ref "PRO_STM32F4DISCOVERY") (pin "42") (pinfunction "PD10/FSMC_D15/USART3_CK_42") (pintype "passive"))
    )
    (net (code "32") (name "/PRO_PD11_SELFTEST") (class "Default")
      (node (ref "PRO_Rdselftest") (pin "1") (pinfunction "1_1") (pintype "passive"))
      (node (ref "PRO_STM32F4DISCOVERY") (pin "43") (pinfunction "PD11/FSMC_A16/USART3_CTS_43") (pintype "passive"))
    )
    (net (code "33") (name "/PRO_PD12_RUN") (class "Default")
      (node (ref "PRO_STM32F4DISCOVERY") (pin "44") (pinfunction "PD12/FSMC_A17/TIM4_CH1/USART3_RTS_44") (pintype "passive"))
    )
    (net (code "34") (name "/PRO_PD13_CAN") (class "Default")
      (node (ref "PRO_STM32F4DISCOVERY") (pin "45") (pinfunction "PD13/FSMC_A18/TIM4_CH2_45") (pintype "passive"))
    )
    (net (code "35") (name "/PRO_PD14_UART") (class "Default")
      (node (ref "PRO_STM32F4DISCOVERY") (pin "46") (pinfunction "PD14/FSMC_D0/TIM4_CH3_46") (pintype "passive"))
    )
    (net (code "36") (name "/PRO_PD15_USER") (class "Default")
      (node (ref "PRO_STM32F4DISCOVERY") (pin "47") (pinfunction "PD15/FSMC_D1/TIM4_CH4_47") (pintype "passive"))
    )
    (net (code "37") (name "/PRO_PE7(RFU)") (class "Default")
      (node (ref "PRO_STM32F4DISCOVERY") (pin "25") (pinfunction "PE7/FSMC_D4/TIM1_ETR_25") (pintype "passive"))
      (node (ref "RFU") (pin "6") (pinfunction "6_6") (pintype "passive"))
    )
    (net (code "38") (name "/PRO_PE8(RFU)") (class "Default")
      (node (ref "PRO_STM32F4DISCOVERY") (pin "26") (pinfunction "PE8/FSMC_D5/TIM1_CH1N_26") (pintype "passive"))
      (node (ref "RFU") (pin "5") (pinfunction "5_5") (pintype "passive"))
    )
    (net (code "39") (name "/PRO_PE9(RFU)") (class "Default")
      (node (ref "PRO_STM32F4DISCOVERY") (pin "27") (pinfunction "PE9/FSMC_D6/TIM1_CH1_27") (pintype "passive"))
      (node (ref "RFU") (pin "4") (pinfunction "4_4") (pintype "passive"))
    )
    (net (code "40") (name "/PRO_PE10(RFU)") (class "Default")
      (node (ref "PRO_STM32F4DISCOVERY") (pin "28") (pinfunction "PE10/FSMC_D7/TIM1_CH2N_28") (pintype "passive"))
      (node (ref "RFU") (pin "3") (pinfunction "3_3") (pintype "passive"))
    )
    (net (code "41") (name "/PRO_PE11(RFU)") (class "Default")
      (node (ref "PRO_STM32F4DISCOVERY") (pin "29") (pinfunction "PE11/FSMC_D8/TIM1_CH2_29") (pintype "passive"))
      (node (ref "RFU") (pin "2") (pinfunction "2_2") (pintype "passive"))
    )
    (net (code "42") (name "/PRO_PE12_CALIBRATION") (class "Default")
      (node (ref "PRO_STM32F4DISCOVERY") (pin "30") (pinfunction "PE12/FSMC_D9/TIM1_CH3N_30") (pintype "passive"))
    )
    (net (code "43") (name "/PRO_U1RX") (class "Default")
      (node (ref "PRO_Rsu1rx") (pin "2") (pinfunction "2_2") (pintype "passive"))
      (node (ref "PRO_UART1") (pin "4") (pinfunction "4_4") (pintype "passive"))
    )
    (net (code "44") (name "/PRO_U1TX") (class "Default")
      (node (ref "PRO_RpuU1tx") (pin "1") (pinfunction "1_1") (pintype "passive"))
      (node (ref "PRO_RsU1tx") (pin "1") (pinfunction "1_1") (pintype "passive"))
      (node (ref "PRO_UART1") (pin "3") (pinfunction "3_3") (pintype "passive"))
    )
    (net (code "45") (name "3V_PRO") (class "Default")
      (node (ref "PRO_RpuDTc1") (pin "2") (pinfunction "2_2") (pintype "passive"))
      (node (ref "PRO_RpuDTc2") (pin "2") (pinfunction "2_2") (pintype "passive"))
      (node (ref "PRO_RpuDTc3") (pin "2") (pinfunction "2_2") (pintype "passive"))
      (node (ref "PRO_RpuDTc4") (pin "2") (pinfunction "2_2") (pintype "passive"))
      (node (ref "PRO_RpuDTd6") (pin "2") (pinfunction "2_2") (pintype "passive"))
      (node (ref "PRO_RpuDTd7") (pin "2") (pinfunction "2_2") (pintype "passive"))
      (node (ref "PRO_RpuU1rx") (pin "2") (pinfunction "2_2") (pintype "passive"))
      (node (ref "PRO_RpuU1tx") (pin "2") (pinfunction "2_2") (pintype "passive"))
      (node (ref "PRO_RupWAmI") (pin "2") (pinfunction "2_2") (pintype "passive"))
      (node (ref "PRO_STM32F4DISCOVERY") (pin "55") (pinfunction "3V_55") (pintype "passive"))
      (node (ref "PRO_STM32F4DISCOVERY") (pin "56") (pinfunction "3V_56") (pintype "passive"))
    )
    (net (code "46") (name "5V") (class "Default")
      (node (ref "PRO_CdCan1") (pin "2") (pinfunction "2_2") (pintype "passive"))
      (node (ref "PRO_CdCan2") (pin "2") (pinfunction "2_2") (pintype "passive"))
      (node (ref "PRO_CdGyro") (pin "2") (pinfunction "2_2") (pintype "passive"))
      (node (ref "PRO_STM32F4DISCOVERY") (pin "53") (pinfunction "5V_53") (pintype "passive"))
      (node (ref "PRO_STM32F4DISCOVERY") (pin "54") (pinfunction "5V_54") (pintype "passive"))
      (node (ref "PRO_Ucan") (pin "3") (pinfunction "VDD_3") (pintype "power_in"))
      (node (ref "PRO_codDroite") (pin "1") (pinfunction "1_1") (pintype "passive"))
      (node (ref "PRO_codDroite") (pin "2") (pinfunction "2_2") (pintype "passive"))
      (node (ref "PRO_codGauche") (pin "1") (pinfunction "1_1") (pintype "passive"))
      (node (ref "PRO_codGauche") (pin "2") (pinfunction "2_2") (pintype "passive"))
      (node (ref "PRO_gyro") (pin "2") (pinfunction "2_2") (pintype "passive"))
    )
    (net (code "47") (name "5V_Perm") (class "Default")
      (node (ref "PRO_UART1") (pin "1") (pinfunction "1_1") (pintype "passive"))
      (node (ref "PRO_UART1") (pin "2") (pinfunction "2_2") (pintype "passive"))
    )
    (net (code "48") (name "24V") (class "Default")
      (node (ref "PRO_CdDtc1") (pin "2") (pinfunction "2_2") (pintype "passive"))
      (node (ref "PRO_CdDtc2") (pin "2") (pinfunction "2_2") (pintype "passive"))
      (node (ref "PRO_CdDtc3") (pin "2") (pinfunction "2_2") (pintype "passive"))
      (node (ref "PRO_CdDtc4") (pin "2") (pinfunction "2_2") (pintype "passive"))
      (node (ref "PRO_CdDtd6") (pin "2") (pinfunction "2_2") (pintype "passive"))
      (node (ref "PRO_CdDtd7") (pin "2") (pinfunction "2_2") (pintype "passive"))
      (node (ref "PRO_DTc1") (pin "3") (pinfunction "3_3") (pintype "passive"))
      (node (ref "PRO_DTc2") (pin "3") (pinfunction "3_3") (pintype "passive"))
      (node (ref "PRO_DTc3") (pin "3") (pinfunction "3_3") (pintype "passive"))
      (node (ref "PRO_DTc4") (pin "3") (pinfunction "3_3") (pintype "passive"))
      (node (ref "PRO_DTd6") (pin "3") (pinfunction "3_3") (pintype "passive"))
      (node (ref "PRO_DTd7") (pin "3") (pinfunction "3_3") (pintype "passive"))
    )
    (net (code "49") (name "GND") (class "Default")
      (node (ref "PRO_CcodDA") (pin "1") (pinfunction "1_1") (pintype "passive"))
      (node (ref "PRO_CcodDB") (pin "1") (pinfunction "1_1") (pintype "passive"))
      (node (ref "PRO_CcodGA") (pin "1") (pinfunction "1_1") (pintype "passive"))
      (node (ref "PRO_CcodGB") (pin "1") (pinfunction "1_1") (pintype "passive"))
      (node (ref "PRO_CdCan1") (pin "1") (pinfunction "1_1") (pintype "passive"))
      (node (ref "PRO_CdCan2") (pin "1") (pinfunction "1_1") (pintype "passive"))
      (node (ref "PRO_CdGyro") (pin "1") (pinfunction "1_1") (pintype "passive"))
      (node (ref "PRO_CfDTc1") (pin "1") (pinfunction "1_1") (pintype "passive"))
      (node (ref "PRO_CfDTc2") (pin "1") (pinfunction "1_1") (pintype "passive"))
      (node (ref "PRO_CfDTc3") (pin "1") (pinfunction "1_1") (pintype "passive"))
      (node (ref "PRO_CfDTc4") (pin "1") (pinfunction "1_1") (pintype "passive"))
      (node (ref "PRO_CfDTd6") (pin "1") (pinfunction "1_1") (pintype "passive"))
      (node (ref "PRO_CfDTd7") (pin "1") (pinfunction "1_1") (pintype "passive"))
      (node (ref "PRO_Cu1rx") (pin "1") (pinfunction "1_1") (pintype "passive"))
      (node (ref "PRO_DSelftest") (pin "2") (pinfunction "K_2") (pintype "passive"))
      (node (ref "PRO_Derror") (pin "2") (pinfunction "K_2") (pintype "passive"))
      (node (ref "PRO_Motors") (pin "3") (pinfunction "3_3") (pintype "passive"))
      (node (ref "PRO_Motors") (pin "4") (pinfunction "4_4") (pintype "passive"))
      (node (ref "PRO_Rdtc1") (pin "1") (pinfunction "1_1") (pintype "passive"))
      (node (ref "PRO_Rdtc2") (pin "1") (pinfunction "1_1") (pintype "passive"))
      (node (ref "PRO_Rdtc3") (pin "1") (pinfunction "1_1") (pintype "passive"))
      (node (ref "PRO_Rdtc4") (pin "1") (pinfunction "1_1") (pintype "passive"))
      (node (ref "PRO_Rdtd6") (pin "1") (pinfunction "1_1") (pintype "passive"))
      (node (ref "PRO_Rdtd7") (pin "1") (pinfunction "1_1") (pintype "passive"))
      (node (ref "PRO_RdwnWAmI") (pin "1") (pinfunction "1_1") (pintype "passive"))
      (node (ref "PRO_STM32F4DISCOVERY") (pin "1") (pinfunction "GND_1") (pintype "passive"))
      (node (ref "PRO_STM32F4DISCOVERY") (pin "100") (pinfunction "GND_100") (pintype "passive"))
      (node (ref "PRO_STM32F4DISCOVERY") (pin "2") (pinfunction "GND_2") (pintype "passive"))
      (node (ref "PRO_STM32F4DISCOVERY") (pin "23") (pinfunction "GND_23") (pintype "passive"))
      (node (ref "PRO_STM32F4DISCOVERY") (pin "49") (pinfunction "GND_49") (pintype "passive"))
      (node (ref "PRO_STM32F4DISCOVERY") (pin "5") (pinfunction "GND_5") (pintype "passive"))
      (node (ref "PRO_STM32F4DISCOVERY") (pin "50") (pinfunction "GND_50") (pintype "passive"))
      (node (ref "PRO_STM32F4DISCOVERY") (pin "51") (pinfunction "GND_51") (pintype "passive"))
      (node (ref "PRO_STM32F4DISCOVERY") (pin "52") (pinfunction "GND_52") (pintype "passive"))
      (node (ref "PRO_STM32F4DISCOVERY") (pin "99") (pinfunction "GND_99") (pintype "passive"))
      (node (ref "PRO_UART1") (pin "5") (pinfunction "5_5") (pintype "passive"))
      (node (ref "PRO_UART1") (pin "6") (pinfunction "6_6") (pintype "passive"))
      (node (ref "PRO_UART2") (pin "1") (pinfunction "1_1") (pintype "passive"))
      (node (ref "PRO_Ucan") (pin "2") (pinfunction "VSS_2") (pintype "power_in"))
      (node (ref "PRO_Ucan") (pin "8") (pinfunction "RS_8") (pintype "input"))
      (node (ref "PRO_codDroite") (pin "5") (pinfunction "5_5") (pintype "passive"))
      (node (ref "PRO_codDroite") (pin "6") (pinfunction "6_6") (pintype "passive"))
      (node (ref "PRO_codGauche") (pin "5") (pinfunction "5_5") (pintype "passive"))
      (node (ref "PRO_codGauche") (pin "6") (pinfunction "6_6") (pintype "passive"))
      (node (ref "PRO_currentMot") (pin "1") (pinfunction "1_1") (pintype "passive"))
      (node (ref "PRO_gyro") (pin "1") (pinfunction "1_1") (pintype "passive"))
      (node (ref "RFU") (pin "1") (pinfunction "1_1") (pintype "passive"))
    )
    (net (code "50") (name "GND_24") (class "Default")
      (node (ref "PRO_CdDtc1") (pin "1") (pinfunction "1_1") (pintype "passive"))
      (node (ref "PRO_CdDtc2") (pin "1") (pinfunction "1_1") (pintype "passive"))
      (node (ref "PRO_CdDtc3") (pin "1") (pinfunction "1_1") (pintype "passive"))
      (node (ref "PRO_CdDtc4") (pin "1") (pinfunction "1_1") (pintype "passive"))
      (node (ref "PRO_CdDtd6") (pin "1") (pinfunction "1_1") (pintype "passive"))
      (node (ref "PRO_CdDtd7") (pin "1") (pinfunction "1_1") (pintype "passive"))
      (node (ref "PRO_DTc1") (pin "1") (pinfunction "1_1") (pintype "passive"))
      (node (ref "PRO_DTc2") (pin "1") (pinfunction "1_1") (pintype "passive"))
      (node (ref "PRO_DTc3") (pin "1") (pinfunction "1_1") (pintype "passive"))
      (node (ref "PRO_DTc4") (pin "1") (pinfunction "1_1") (pintype "passive"))
      (node (ref "PRO_DTd6") (pin "1") (pinfunction "1_1") (pintype "passive"))
      (node (ref "PRO_DTd7") (pin "1") (pinfunction "1_1") (pintype "passive"))
    )
    (net (code "51") (name "Net-(PRO_DSelftest-A)") (class "Default")
      (node (ref "PRO_DSelftest") (pin "1") (pinfunction "A_1") (pintype "passive"))
      (node (ref "PRO_Rdselftest") (pin "2") (pinfunction "2_2") (pintype "passive"))
    )
    (net (code "52") (name "Net-(PRO_DTc1-Pad2)") (class "Default")
      (node (ref "PRO_DTc1") (pin "2") (pinfunction "2_2") (pintype "passive"))
      (node (ref "PRO_Rdtc1") (pin "2") (pinfunction "2_2") (pintype "passive"))
      (node (ref "PRO_RfDTc1") (pin "1") (pinfunction "1_1") (pintype "passive"))
    )
    (net (code "53") (name "Net-(PRO_DTc2-Pad2)") (class "Default")
      (node (ref "PRO_DTc2") (pin "2") (pinfunction "2_2") (pintype "passive"))
      (node (ref "PRO_Rdtc2") (pin "2") (pinfunction "2_2") (pintype "passive"))
      (node (ref "PRO_RfDTc2") (pin "1") (pinfunction "1_1") (pintype "passive"))
    )
    (net (code "54") (name "Net-(PRO_DTc3-Pad2)") (class "Default")
      (node (ref "PRO_DTc3") (pin "2") (pinfunction "2_2") (pintype "passive"))
      (node (ref "PRO_Rdtc3") (pin "2") (pinfunction "2_2") (pintype "passive"))
      (node (ref "PRO_RfDTc3") (pin "1") (pinfunction "1_1") (pintype "passive"))
    )
    (net (code "55") (name "Net-(PRO_DTc4-Pad2)") (class "Default")
      (node (ref "PRO_DTc4") (pin "2") (pinfunction "2_2") (pintype "passive"))
      (node (ref "PRO_Rdtc4") (pin "2") (pinfunction "2_2") (pintype "passive"))
      (node (ref "PRO_RfDTc4") (pin "1") (pinfunction "1_1") (pintype "passive"))
    )
    (net (code "56") (name "Net-(PRO_DTd6-Pad2)") (class "Default")
      (node (ref "PRO_DTd6") (pin "2") (pinfunction "2_2") (pintype "passive"))
      (node (ref "PRO_Rdtd6") (pin "2") (pinfunction "2_2") (pintype "passive"))
      (node (ref "PRO_RfDTd6") (pin "1") (pinfunction "1_1") (pintype "passive"))
    )
    (net (code "57") (name "Net-(PRO_DTd7-Pad2)") (class "Default")
      (node (ref "PRO_DTd7") (pin "2") (pinfunction "2_2") (pintype "passive"))
      (node (ref "PRO_Rdtd7") (pin "2") (pinfunction "2_2") (pintype "passive"))
      (node (ref "PRO_RfDTd7") (pin "1") (pinfunction "1_1") (pintype "passive"))
    )
    (net (code "58") (name "Net-(PRO_Derror-A)") (class "Default")
      (node (ref "PRO_Derror") (pin "1") (pinfunction "A_1") (pintype "passive"))
      (node (ref "PRO_Rderror") (pin "2") (pinfunction "2_2") (pintype "passive"))
    )
    (net (code "59") (name "Net-(PRO_RCodDA-Pad2)") (class "Default")
      (node (ref "PRO_RCodDA") (pin "2") (pinfunction "2_2") (pintype "passive"))
      (node (ref "PRO_codDroite") (pin "4") (pinfunction "4_4") (pintype "passive"))
    )
    (net (code "60") (name "Net-(PRO_RCodDB-Pad2)") (class "Default")
      (node (ref "PRO_RCodDB") (pin "2") (pinfunction "2_2") (pintype "passive"))
      (node (ref "PRO_codDroite") (pin "3") (pinfunction "3_3") (pintype "passive"))
    )
    (net (code "61") (name "Net-(PRO_RCodGA-Pad2)") (class "Default")
      (node (ref "PRO_RCodGA") (pin "2") (pinfunction "2_2") (pintype "passive"))
      (node (ref "PRO_codGauche") (pin "4") (pinfunction "4_4") (pintype "passive"))
    )
    (net (code "62") (name "Net-(PRO_RCodGB-Pad2)") (class "Default")
      (node (ref "PRO_RCodGB") (pin "2") (pinfunction "2_2") (pintype "passive"))
      (node (ref "PRO_codGauche") (pin "3") (pinfunction "3_3") (pintype "passive"))
    )
    (net (code "63") (name "unconnected-(PRO_STM32F4DISCOVERY-BOOT0{slash}VPP-Pad71)") (class "Default")
      (node (ref "PRO_STM32F4DISCOVERY") (pin "71") (pinfunction "BOOT0/VPP_71") (pintype "passive+no_connect"))
    )
    (net (code "64") (name "unconnected-(PRO_STM32F4DISCOVERY-NC-Pad48)") (class "Default")
      (node (ref "PRO_STM32F4DISCOVERY") (pin "48") (pinfunction "NC_48") (pintype "passive+no_connect"))
    )
    (net (code "65") (name "unconnected-(PRO_STM32F4DISCOVERY-NRST-Pad6)") (class "Default")
      (node (ref "PRO_STM32F4DISCOVERY") (pin "6") (pinfunction "NRST_6") (pintype "passive+no_connect"))
    )
    (net (code "66") (name "unconnected-(PRO_STM32F4DISCOVERY-PA0-WKUP{slash}USART2_CTS{slash}USART4_TX{slash}ETH_MII_CRS{slash}TIM2_CH1_ETR{slash}TIM5_CH1{slash}TIM8_ETR{slash}ADC123_IN0{slash}WKUP-Pad12)") (class "Default")
      (node (ref "PRO_STM32F4DISCOVERY") (pin "12") (pinfunction "PA0-WKUP/USART2_CTS/USART4_TX/ETH_MII_CRS/TIM2_CH1_ETR/TIM5_CH1/TIM8_ETR/ADC123_IN0/WKUP_12") (pintype "passive+no_connect"))
    )
    (net (code "67") (name "unconnected-(PRO_STM32F4DISCOVERY-PA4{slash}SPI1_NSS{slash}SPI3_NSS{slash}USART2_CK{slash}DCMI_HSYNC{slash}OTG_HS_SOF{slash}I2S3_WS{slash}ADC12_IN4{slash}DAC1_OUT-Pad16)") (class "Default")
      (node (ref "PRO_STM32F4DISCOVERY") (pin "16") (pinfunction "PA4/SPI1_NSS/SPI3_NSS/USART2_CK/DCMI_HSYNC/OTG_HS_SOF/I2S3_WS/ADC12_IN4/DAC1_OUT_16") (pintype "passive+no_connect"))
    )
    (net (code "68") (name "unconnected-(PRO_STM32F4DISCOVERY-PA5{slash}SPI1_SCK{slash}OTG_HS_ULPI_CK{slash}TIM2_CH1_ETR{slash}TIM8_CHIN{slash}ADC12_IN5{slash}DAC2_OUT-Pad15)") (class "Default")
      (node (ref "PRO_STM32F4DISCOVERY") (pin "15") (pinfunction "PA5/SPI1_SCK/OTG_HS_ULPI_CK/TIM2_CH1_ETR/TIM8_CHIN/ADC12_IN5/DAC2_OUT_15") (pintype "passive+no_connect"))
    )
    (net (code "69") (name "unconnected-(PRO_STM32F4DISCOVERY-PA6{slash}SPI1_MISO{slash}TIM8_BKIN{slash}TIM13_CH1{slash}DCMI_PIXCLK{slash}TIM3_CH1{slash}TIM1_BKIN{slash}ADC12_IN6-Pad18)") (class "Default")
      (node (ref "PRO_STM32F4DISCOVERY") (pin "18") (pinfunction "PA6/SPI1_MISO/TIM8_BKIN/TIM13_CH1/DCMI_PIXCLK/TIM3_CH1/TIM1_BKIN/ADC12_IN6_18") (pintype "passive+no_connect"))
    )
    (net (code "70") (name "unconnected-(PRO_STM32F4DISCOVERY-PA7{slash}SPI1_MOSI{slash}TIM8_CH1N{slash}TIM14_CH1TIM3_CH2{slash}ETH_MII_RX_DV{slash}TIM1_CH1N{slash}RMII_CRS_DV{slash}ADC12_IN7-Pad17)") (class "Default")
      (node (ref "PRO_STM32F4DISCOVERY") (pin "17") (pinfunction "PA7/SPI1_MOSI/TIM8_CH1N/TIM14_CH1TIM3_CH2/ETH_MII_RX_DV/TIM1_CH1N/RMII_CRS_DV/ADC12_IN7_17") (pintype "passive+no_connect"))
    )
    (net (code "71") (name "unconnected-(PRO_STM32F4DISCOVERY-PA8{slash}MCO1{slash}USART1_CK{slash}TIM1_CH1{slash}I2C3_SCL{slash}OTG_FS_SOF-Pad93)") (class "Default")
      (node (ref "PRO_STM32F4DISCOVERY") (pin "93") (pinfunction "PA8/MCO1/USART1_CK/TIM1_CH1/I2C3_SCL/OTG_FS_SOF_93") (pintype "passive+no_connect"))
    )
    (net (code "72") (name "unconnected-(PRO_STM32F4DISCOVERY-PA9{slash}USART1_TX{slash}TIM1_CH2{slash}I2C3_SMBA{slash}DCMI_D0{slash}OTG_FS_VBUS-Pad94)") (class "Default")
      (node (ref "PRO_STM32F4DISCOVERY") (pin "94") (pinfunction "PA9/USART1_TX/TIM1_CH2/I2C3_SMBA/DCMI_D0/OTG_FS_VBUS_94") (pintype "passive+no_connect"))
    )
    (net (code "73") (name "unconnected-(PRO_STM32F4DISCOVERY-PA10{slash}USART1_RX{slash}TIM1_CH3{slash}OTG_FS_ID{slash}DCMI_D1-Pad91)") (class "Default")
      (node (ref "PRO_STM32F4DISCOVERY") (pin "91") (pinfunction "PA10/USART1_RX/TIM1_CH3/OTG_FS_ID/DCMI_D1_91") (pintype "passive+no_connect"))
    )
    (net (code "74") (name "unconnected-(PRO_STM32F4DISCOVERY-PA13{slash}JTMS_SWDIO-Pad92)") (class "Default")
      (node (ref "PRO_STM32F4DISCOVERY") (pin "92") (pinfunction "PA13/JTMS_SWDIO_92") (pintype "passive+no_connect"))
    )
    (net (code "75") (name "unconnected-(PRO_STM32F4DISCOVERY-PA14{slash}JTCK_SWCLK-Pad89)") (class "Default")
      (node (ref "PRO_STM32F4DISCOVERY") (pin "89") (pinfunction "PA14/JTCK_SWCLK_89") (pintype "passive+no_connect"))
    )
    (net (code "76") (name "unconnected-(PRO_STM32F4DISCOVERY-PB2-Pad24)") (class "Default")
      (node (ref "PRO_STM32F4DISCOVERY") (pin "24") (pinfunction "PB2_24") (pintype "passive+no_connect"))
    )
    (net (code "77") (name "unconnected-(PRO_STM32F4DISCOVERY-PB3{slash}JTDO{slash}TRACESWO{slash}SPI3_SCK{slash}I2S3_CK{slash}TIM2_CH2{slash}SPI1_SCK-Pad78)") (class "Default")
      (node (ref "PRO_STM32F4DISCOVERY") (pin "78") (pinfunction "PB3/JTDO/TRACESWO/SPI3_SCK/I2S3_CK/TIM2_CH2/SPI1_SCK_78") (pintype "passive+no_connect"))
    )
    (net (code "78") (name "unconnected-(PRO_STM32F4DISCOVERY-PB9{slash}SPI2_NSS{slash}I2S2_WS{slash}TIM4_CH4{slash}TIM11_CH1{slash}OTG_FS_SDA{slash}SDIO_D5{slash}DCMI_D7{slash}I2C1_SDA{slash}CAN1_TX-Pad70)") (class "Default")
      (node (ref "PRO_STM32F4DISCOVERY") (pin "70") (pinfunction "PB9/SPI2_NSS/I2S2_WS/TIM4_CH4/TIM11_CH1/OTG_FS_SDA/SDIO_D5/DCMI_D7/I2C1_SDA/CAN1_TX_70") (pintype "passive+no_connect"))
    )
    (net (code "79") (name "unconnected-(PRO_STM32F4DISCOVERY-PB10{slash}SPI2_SCK{slash}I2S2_CK{slash}I2C2_SCL{slash}USART3_TX{slash}OTG_HS_ULPI_D3{slash}ETH_MII_RX_ER{slash}OTG_HS_SCL{slash}TIM2_CH3-Pad34)") (class "Default")
      (node (ref "PRO_STM32F4DISCOVERY") (pin "34") (pinfunction "PB10/SPI2_SCK/I2S2_CK/I2C2_SCL/USART3_TX/OTG_HS_ULPI_D3/ETH_MII_RX_ER/OTG_HS_SCL/TIM2_CH3_34") (pintype "passive+no_connect"))
    )
    (net (code "80") (name "unconnected-(PRO_STM32F4DISCOVERY-PB11{slash}I2C2_SDA{slash}USART3_RX{slash}OTG_HS_ULPI_D4{slash}ETH_RMII_TX_EN{slash}ETH_MII_TX_EN{slash}OTG_HS_SDA{slash}TIM2_CH4-Pad35)") (class "Default")
      (node (ref "PRO_STM32F4DISCOVERY") (pin "35") (pinfunction "PB11/I2C2_SDA/USART3_RX/OTG_HS_ULPI_D4/ETH_RMII_TX_EN/ETH_MII_TX_EN/OTG_HS_SDA/TIM2_CH4_35") (pintype "passive+no_connect"))
    )
    (net (code "81") (name "unconnected-(PRO_STM32F4DISCOVERY-PC0{slash}OTG_HS_ULPI_STP{slash}ADC123_IN10-Pad8)") (class "Default")
      (node (ref "PRO_STM32F4DISCOVERY") (pin "8") (pinfunction "PC0/OTG_HS_ULPI_STP/ADC123_IN10_8") (pintype "passive+no_connect"))
    )
    (net (code "82") (name "unconnected-(PRO_STM32F4DISCOVERY-PC5{slash}ETH_RMII_RX_D1{slash}ETH_MII_RX_D1{slash}ADC12_IN15-Pad19)") (class "Default")
      (node (ref "PRO_STM32F4DISCOVERY") (pin "19") (pinfunction "PC5/ETH_RMII_RX_D1/ETH_MII_RX_D1/ADC12_IN15_19") (pintype "passive+no_connect"))
    )
    (net (code "83") (name "unconnected-(PRO_STM32F4DISCOVERY-PC6{slash}I2S2_MCK{slash}TIM8_CH1{slash}SDIO_D6{slash}USART6_TX{slash}DCMI_D0{slash}TIM3_CH1-Pad97)") (class "Default")
      (node (ref "PRO_STM32F4DISCOVERY") (pin "97") (pinfunction "PC6/I2S2_MCK/TIM8_CH1/SDIO_D6/USART6_TX/DCMI_D0/TIM3_CH1_97") (pintype "passive+no_connect"))
    )
    (net (code "84") (name "unconnected-(PRO_STM32F4DISCOVERY-PC7{slash}I2S3_MCK{slash}TIM8_CH2{slash}SDIO_D7{slash}USART6_RX_DCMI_D1{slash}TIM3_CH2-Pad98)") (class "Default")
      (node (ref "PRO_STM32F4DISCOVERY") (pin "98") (pinfunction "PC7/I2S3_MCK/TIM8_CH2/SDIO_D7/USART6_RX_DCMI_D1/TIM3_CH2_98") (pintype "passive+no_connect"))
    )
    (net (code "85") (name "unconnected-(PRO_STM32F4DISCOVERY-PC10{slash}SPI3_SCK{slash}I2S3_CK{slash}UART4_TX{slash}SDIO_D2{slash}DCMI_D8{slash}USART3_TX-Pad87)") (class "Default")
      (node (ref "PRO_STM32F4DISCOVERY") (pin "87") (pinfunction "PC10/SPI3_SCK/I2S3_CK/UART4_TX/SDIO_D2/DCMI_D8/USART3_TX_87") (pintype "passive+no_connect"))
    )
    (net (code "86") (name "unconnected-(PRO_STM32F4DISCOVERY-PC14{slash}OSC32_IN-Pad59)") (class "Default")
      (node (ref "PRO_STM32F4DISCOVERY") (pin "59") (pinfunction "PC14/OSC32_IN_59") (pintype "passive+no_connect"))
    )
    (net (code "87") (name "unconnected-(PRO_STM32F4DISCOVERY-PC15{slash}OSC32_OUT-Pad60)") (class "Default")
      (node (ref "PRO_STM32F4DISCOVERY") (pin "60") (pinfunction "PC15/OSC32_OUT_60") (pintype "passive+no_connect"))
    )
    (net (code "88") (name "unconnected-(PRO_STM32F4DISCOVERY-PD2{slash}TIM3_ETR{slash}UART5_RXSDIO_CMD{slash}DCMI_D11-Pad84)") (class "Default")
      (node (ref "PRO_STM32F4DISCOVERY") (pin "84") (pinfunction "PD2/TIM3_ETR/UART5_RXSDIO_CMD/DCMI_D11_84") (pintype "passive+no_connect"))
    )
    (net (code "89") (name "unconnected-(PRO_STM32F4DISCOVERY-PD3{slash}FSMC_CLK{slash}USART2_CTS-Pad81)") (class "Default")
      (node (ref "PRO_STM32F4DISCOVERY") (pin "81") (pinfunction "PD3/FSMC_CLK/USART2_CTS_81") (pintype "passive+no_connect"))
    )
    (net (code "90") (name "unconnected-(PRO_STM32F4DISCOVERY-PD4{slash}FSMC_NOE{slash}USART2_RTS-Pad82)") (class "Default")
      (node (ref "PRO_STM32F4DISCOVERY") (pin "82") (pinfunction "PD4/FSMC_NOE/USART2_RTS_82") (pintype "passive+no_connect"))
    )
    (net (code "91") (name "unconnected-(PRO_STM32F4DISCOVERY-PD5{slash}FSMC_NWE{slash}USART2_TX-Pad79)") (class "Default")
      (node (ref "PRO_STM32F4DISCOVERY") (pin "79") (pinfunction "PD5/FSMC_NWE/USART2_TX_79") (pintype "passive+no_connect"))
    )
    (net (code "92") (name "unconnected-(PRO_STM32F4DISCOVERY-PD8{slash}FSMC_D13{slash}USART3_TX-Pad40)") (class "Default")
      (node (ref "PRO_STM32F4DISCOVERY") (pin "40") (pinfunction "PD8/FSMC_D13/USART3_TX_40") (pintype "passive+no_connect"))
    )
    (net (code "93") (name "unconnected-(PRO_STM32F4DISCOVERY-PD9{slash}FSMC_D14{slash}USART3_RX-Pad41)") (class "Default")
      (node (ref "PRO_STM32F4DISCOVERY") (pin "41") (pinfunction "PD9/FSMC_D14/USART3_RX_41") (pintype "passive+no_connect"))
    )
    (net (code "94") (name "unconnected-(PRO_STM32F4DISCOVERY-PE0{slash}TIM4_ETR{slash}FSMC_NBL0{slash}DCMI_D2-Pad67)") (class "Default")
      (node (ref "PRO_STM32F4DISCOVERY") (pin "67") (pinfunction "PE0/TIM4_ETR/FSMC_NBL0/DCMI_D2_67") (pintype "passive+no_connect"))
    )
    (net (code "95") (name "unconnected-(PRO_STM32F4DISCOVERY-PE1{slash}FSMC_NBL1{slash}DCMI_D3-Pad68)") (class "Default")
      (node (ref "PRO_STM32F4DISCOVERY") (pin "68") (pinfunction "PE1/FSMC_NBL1/DCMI_D3_68") (pintype "passive+no_connect"))
    )
    (net (code "96") (name "unconnected-(PRO_STM32F4DISCOVERY-PE2{slash}TRACECLK{slash}FSMC_A23{slash}ETH_MII_TXD3-Pad65)") (class "Default")
      (node (ref "PRO_STM32F4DISCOVERY") (pin "65") (pinfunction "PE2/TRACECLK/FSMC_A23/ETH_MII_TXD3_65") (pintype "passive+no_connect"))
    )
    (net (code "97") (name "unconnected-(PRO_STM32F4DISCOVERY-PE3{slash}TRACED0{slash}FSMC_A19-Pad66)") (class "Default")
      (node (ref "PRO_STM32F4DISCOVERY") (pin "66") (pinfunction "PE3/TRACED0/FSMC_A19_66") (pintype "passive+no_connect"))
    )
    (net (code "98") (name "unconnected-(PRO_STM32F4DISCOVERY-PE4{slash}TRACED1{slash}FSMC_A20{slash}DCMI_D4-Pad63)") (class "Default")
      (node (ref "PRO_STM32F4DISCOVERY") (pin "63") (pinfunction "PE4/TRACED1/FSMC_A20/DCMI_D4_63") (pintype "passive+no_connect"))
    )
    (net (code "99") (name "unconnected-(PRO_STM32F4DISCOVERY-PE5{slash}TRACED2{slash}FSMC_A21{slash}TIM9_CH1{slash}DCMI_D6-Pad64)") (class "Default")
      (node (ref "PRO_STM32F4DISCOVERY") (pin "64") (pinfunction "PE5/TRACED2/FSMC_A21/TIM9_CH1/DCMI_D6_64") (pintype "passive+no_connect"))
    )
    (net (code "100") (name "unconnected-(PRO_STM32F4DISCOVERY-PE6{slash}TRACED3{slash}FSMC_A22{slash}TIM9_CH2{slash}DCMI_D7-Pad61)") (class "Default")
      (node (ref "PRO_STM32F4DISCOVERY") (pin "61") (pinfunction "PE6/TRACED3/FSMC_A22/TIM9_CH2/DCMI_D7_61") (pintype "passive+no_connect"))
    )
    (net (code "101") (name "unconnected-(PRO_STM32F4DISCOVERY-PE13{slash}FSMC_D10{slash}TIM1_CH3-Pad31)") (class "Default")
      (node (ref "PRO_STM32F4DISCOVERY") (pin "31") (pinfunction "PE13/FSMC_D10/TIM1_CH3_31") (pintype "passive+no_connect"))
    )
    (net (code "102") (name "unconnected-(PRO_STM32F4DISCOVERY-PE14{slash}FSMC_D11{slash}TIM1_CH4-Pad32)") (class "Default")
      (node (ref "PRO_STM32F4DISCOVERY") (pin "32") (pinfunction "PE14/FSMC_D11/TIM1_CH4_32") (pintype "passive+no_connect"))
    )
    (net (code "103") (name "unconnected-(PRO_STM32F4DISCOVERY-PE15{slash}FSMC_D12{slash}TIM1_BKIN-Pad33)") (class "Default")
      (node (ref "PRO_STM32F4DISCOVERY") (pin "33") (pinfunction "PE15/FSMC_D12/TIM1_BKIN_33") (pintype "passive+no_connect"))
    )
    (net (code "104") (name "unconnected-(PRO_STM32F4DISCOVERY-PH0{slash}OSC_IN-Pad57)") (class "Default")
      (node (ref "PRO_STM32F4DISCOVERY") (pin "57") (pinfunction "PH0/OSC_IN_57") (pintype "passive+no_connect"))
    )
    (net (code "105") (name "unconnected-(PRO_STM32F4DISCOVERY-PH1{slash}OSC_OUT-Pad58)") (class "Default")
      (node (ref "PRO_STM32F4DISCOVERY") (pin "58") (pinfunction "PH1/OSC_OUT_58") (pintype "passive+no_connect"))
    )
    (net (code "106") (name "unconnected-(PRO_STM32F4DISCOVERY-VDD-Pad3)") (class "Default")
      (node (ref "PRO_STM32F4DISCOVERY") (pin "3") (pinfunction "VDD_3") (pintype "passive+no_connect"))
    )
    (net (code "107") (name "unconnected-(PRO_STM32F4DISCOVERY-VDD-Pad4)") (class "Default")
      (node (ref "PRO_STM32F4DISCOVERY") (pin "4") (pinfunction "VDD_4") (pintype "passive+no_connect"))
    )
    (net (code "108") (name "unconnected-(PRO_STM32F4DISCOVERY-VDD-Pad72)") (class "Default")
      (node (ref "PRO_STM32F4DISCOVERY") (pin "72") (pinfunction "VDD_72") (pintype "passive+no_connect"))
    )
    (net (code "109") (name "unconnected-(PRO_Ucan-VREF-Pad5)") (class "Default")
      (node (ref "PRO_Ucan") (pin "5") (pinfunction "VREF_5") (pintype "output+no_connect"))
    )
  )
)
